# Battery_Charger.net
KiCad netlist of a schematic drawn in Altium Designer
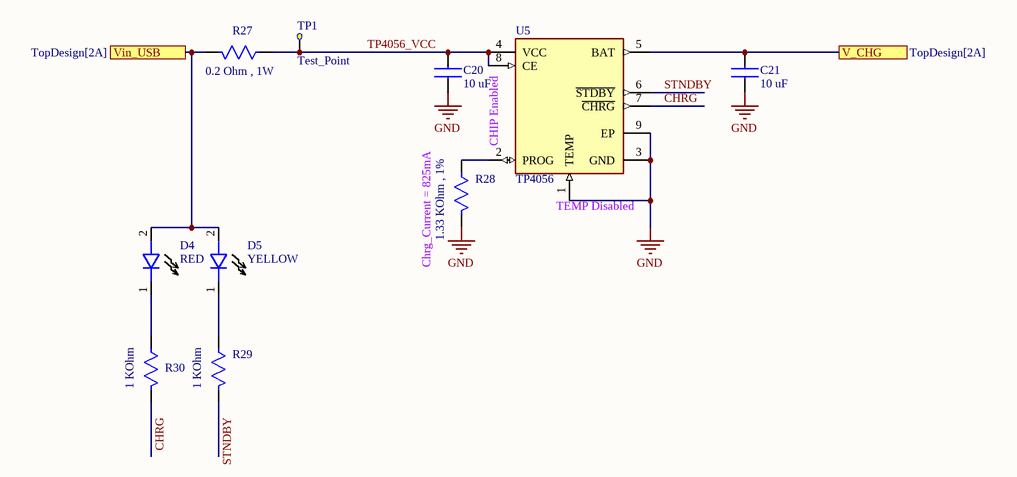
[diagram p0: Battery_Charger.SchDoc]

(export (version "E")
  (design (tool "Eeschema 10.0.6"))
  (components
    (comp (ref "C20")
      (value "10 uF")
      (footprint "CAP_0603")
      (description "Cap Ceramic 1uF 10V X5R 10% Pad SMD 0402 85C T/R")
      (fields
        (field (name "MANUFACTURER_PART_NUMBER") "CL05A105KP5NNNC")
        (field (name "MOUSER PART NUMBER") "187-CL05A105KP5NNNC")
      )
      (libsource (lib "Aptinex_discrete") (part "Cap_SMD_New"))
    )
    (comp (ref "C21")
      (value "10 uF")
      (footprint "CAP_0603")
      (description "Cap Ceramic 1uF 10V X5R 10% Pad SMD 0402 85C T/R")
      (fields
        (field (name "MANUFACTURER_PART_NUMBER") "CL05A105KP5NNNC")
        (field (name "MOUSER PART NUMBER") "187-CL05A105KP5NNNC")
      )
      (libsource (lib "Aptinex_discrete") (part "Cap_SMD_New"))
    )
    (comp (ref "D4")
      (value "RED")
      (footprint "LED SMD 0603")
      (description "SMD LED")
      (libsource (lib "Aptinex_discrete") (part "LED SMD"))
    )
    (comp (ref "D5")
      (value "YELLOW")
      (footprint "LED SMD 0603")
      (description "SMD LED")
      (libsource (lib "Aptinex_discrete") (part "LED SMD"))
    )
    (comp (ref "R27")
      (value "0.2 Ohm , 1W")
      (footprint "RES_2512")
      (description "SMD Resistor")
      (fields (field (name "MP") "RC0805FR-07330RL") (field (name "MF") "Yageo"))
      (libsource (lib "Aptinex_discrete") (part "Res smd"))
    )
    (comp (ref "R28")
      (value "1.33 KOhm , 1%")
      (footprint "Res_0603")
      (description "SMD Resistor")
      (fields (field (name "MP") "RC0805FR-07330RL") (field (name "MF") "Yageo"))
      (libsource (lib "Aptinex_discrete") (part "Res smd"))
    )
    (comp (ref "R29")
      (value "1 KOhm")
      (footprint "Res_0603")
      (description "SMD Resistor")
      (fields (field (name "MP") "RC0805FR-07330RL") (field (name "MF") "Yageo"))
      (libsource (lib "Aptinex_discrete") (part "Res smd"))
    )
    (comp (ref "R30")
      (value "1 KOhm")
      (footprint "Res_0603")
      (description "SMD Resistor")
      (fields (field (name "MP") "RC0805FR-07330RL") (field (name "MF") "Yageo"))
      (libsource (lib "Aptinex_discrete") (part "Res smd"))
    )
    (comp (ref "TP1")
      (value "Test_Point")
      (footprint "Test_Point")
      (libsource (lib "Aptinex_discrete") (part "Test_Point"))
    )
    (comp (ref "U5")
      (value "TP4056")
      (footprint "TP4056-SOP-8-EP")
      (libsource (lib "Aptinex_devices") (part "TP4056"))
    )
  )
  (nets
    (net (code "1") (name "/CHRG") (class "Default")
      (node (ref "R30") (pin "1") (pinfunction "1_1") (pintype "passive"))
      (node (ref "U5") (pin "7") (pinfunction "~{CHRG}_7") (pintype "output"))
    )
    (net (code "2") (name "/STNDBY") (class "Default")
      (node (ref "R29") (pin "1") (pinfunction "1_1") (pintype "passive"))
      (node (ref "U5") (pin "6") (pinfunction "~{STDBY}_6") (pintype "output"))
    )
    (net (code "3") (name "/TP4056_VCC") (class "Default")
      (node (ref "C20") (pin "2") (pinfunction "2_2") (pintype "passive"))
      (node (ref "R27") (pin "2") (pinfunction "2_2") (pintype "passive"))
      (node (ref "TP1") (pin "TP?") (pinfunction "Ref_Point_TP?") (pintype "passive"))
      (node (ref "U5") (pin "4") (pinfunction "VCC_4") (pintype "power_in"))
      (node (ref "U5") (pin "8") (pinfunction "CE_8") (pintype "input"))
    )
    (net (code "4") (name "/V_CHG") (class "Default")
      (node (ref "C21") (pin "2") (pinfunction "2_2") (pintype "passive"))
      (node (ref "U5") (pin "5") (pinfunction "BAT_5") (pintype "output"))
    )
    (net (code "5") (name "/Vin_USB") (class "Default")
      (node (ref "D4") (pin "2") (pinfunction "2_2") (pintype "passive"))
      (node (ref "D5") (pin "2") (pinfunction "2_2") (pintype "passive"))
      (node (ref "R27") (pin "1") (pinfunction "1_1") (pintype "passive"))
    )
    (net (code "6") (name "GND") (class "Default")
      (node (ref "C20") (pin "1") (pinfunction "1_1") (pintype "passive"))
      (node (ref "C21") (pin "1") (pinfunction "1_1") (pintype "passive"))
      (node (ref "R28") (pin "1") (pinfunction "1_1") (pintype "passive"))
      (node (ref "U5") (pin "1") (pinfunction "TEMP_1") (pintype "input"))
      (node (ref "U5") (pin "3") (pinfunction "GND_3") (pintype "power_in"))
      (node (ref "U5") (pin "9") (pinfunction "EP_9") (pintype "passive"))
    )
    (net (code "7") (name "Net-(D4-Pad1)") (class "Default")
      (node (ref "D4") (pin "1") (pinfunction "1_1") (pintype "passive"))
      (node (ref "R30") (pin "2") (pinfunction "2_2") (pintype "passive"))
    )
    (net (code "8") (name "Net-(D5-Pad1)") (class "Default")
      (node (ref "D5") (pin "1") (pinfunction "1_1") (pintype "passive"))
      (node (ref "R29") (pin "2") (pinfunction "2_2") (pintype "passive"))
    )
    (net (code "9") (name "Net-(U5-PROG)") (class "Default")
      (node (ref "R28") (pin "2") (pinfunction "2_2") (pintype "passive"))
      (node (ref "U5") (pin "2") (pinfunction "PROG_2") (pintype "bidirectional"))
    )
  )
)
